# Sheet2.net
KiCad netlist of a schematic drawn in Altium Designer
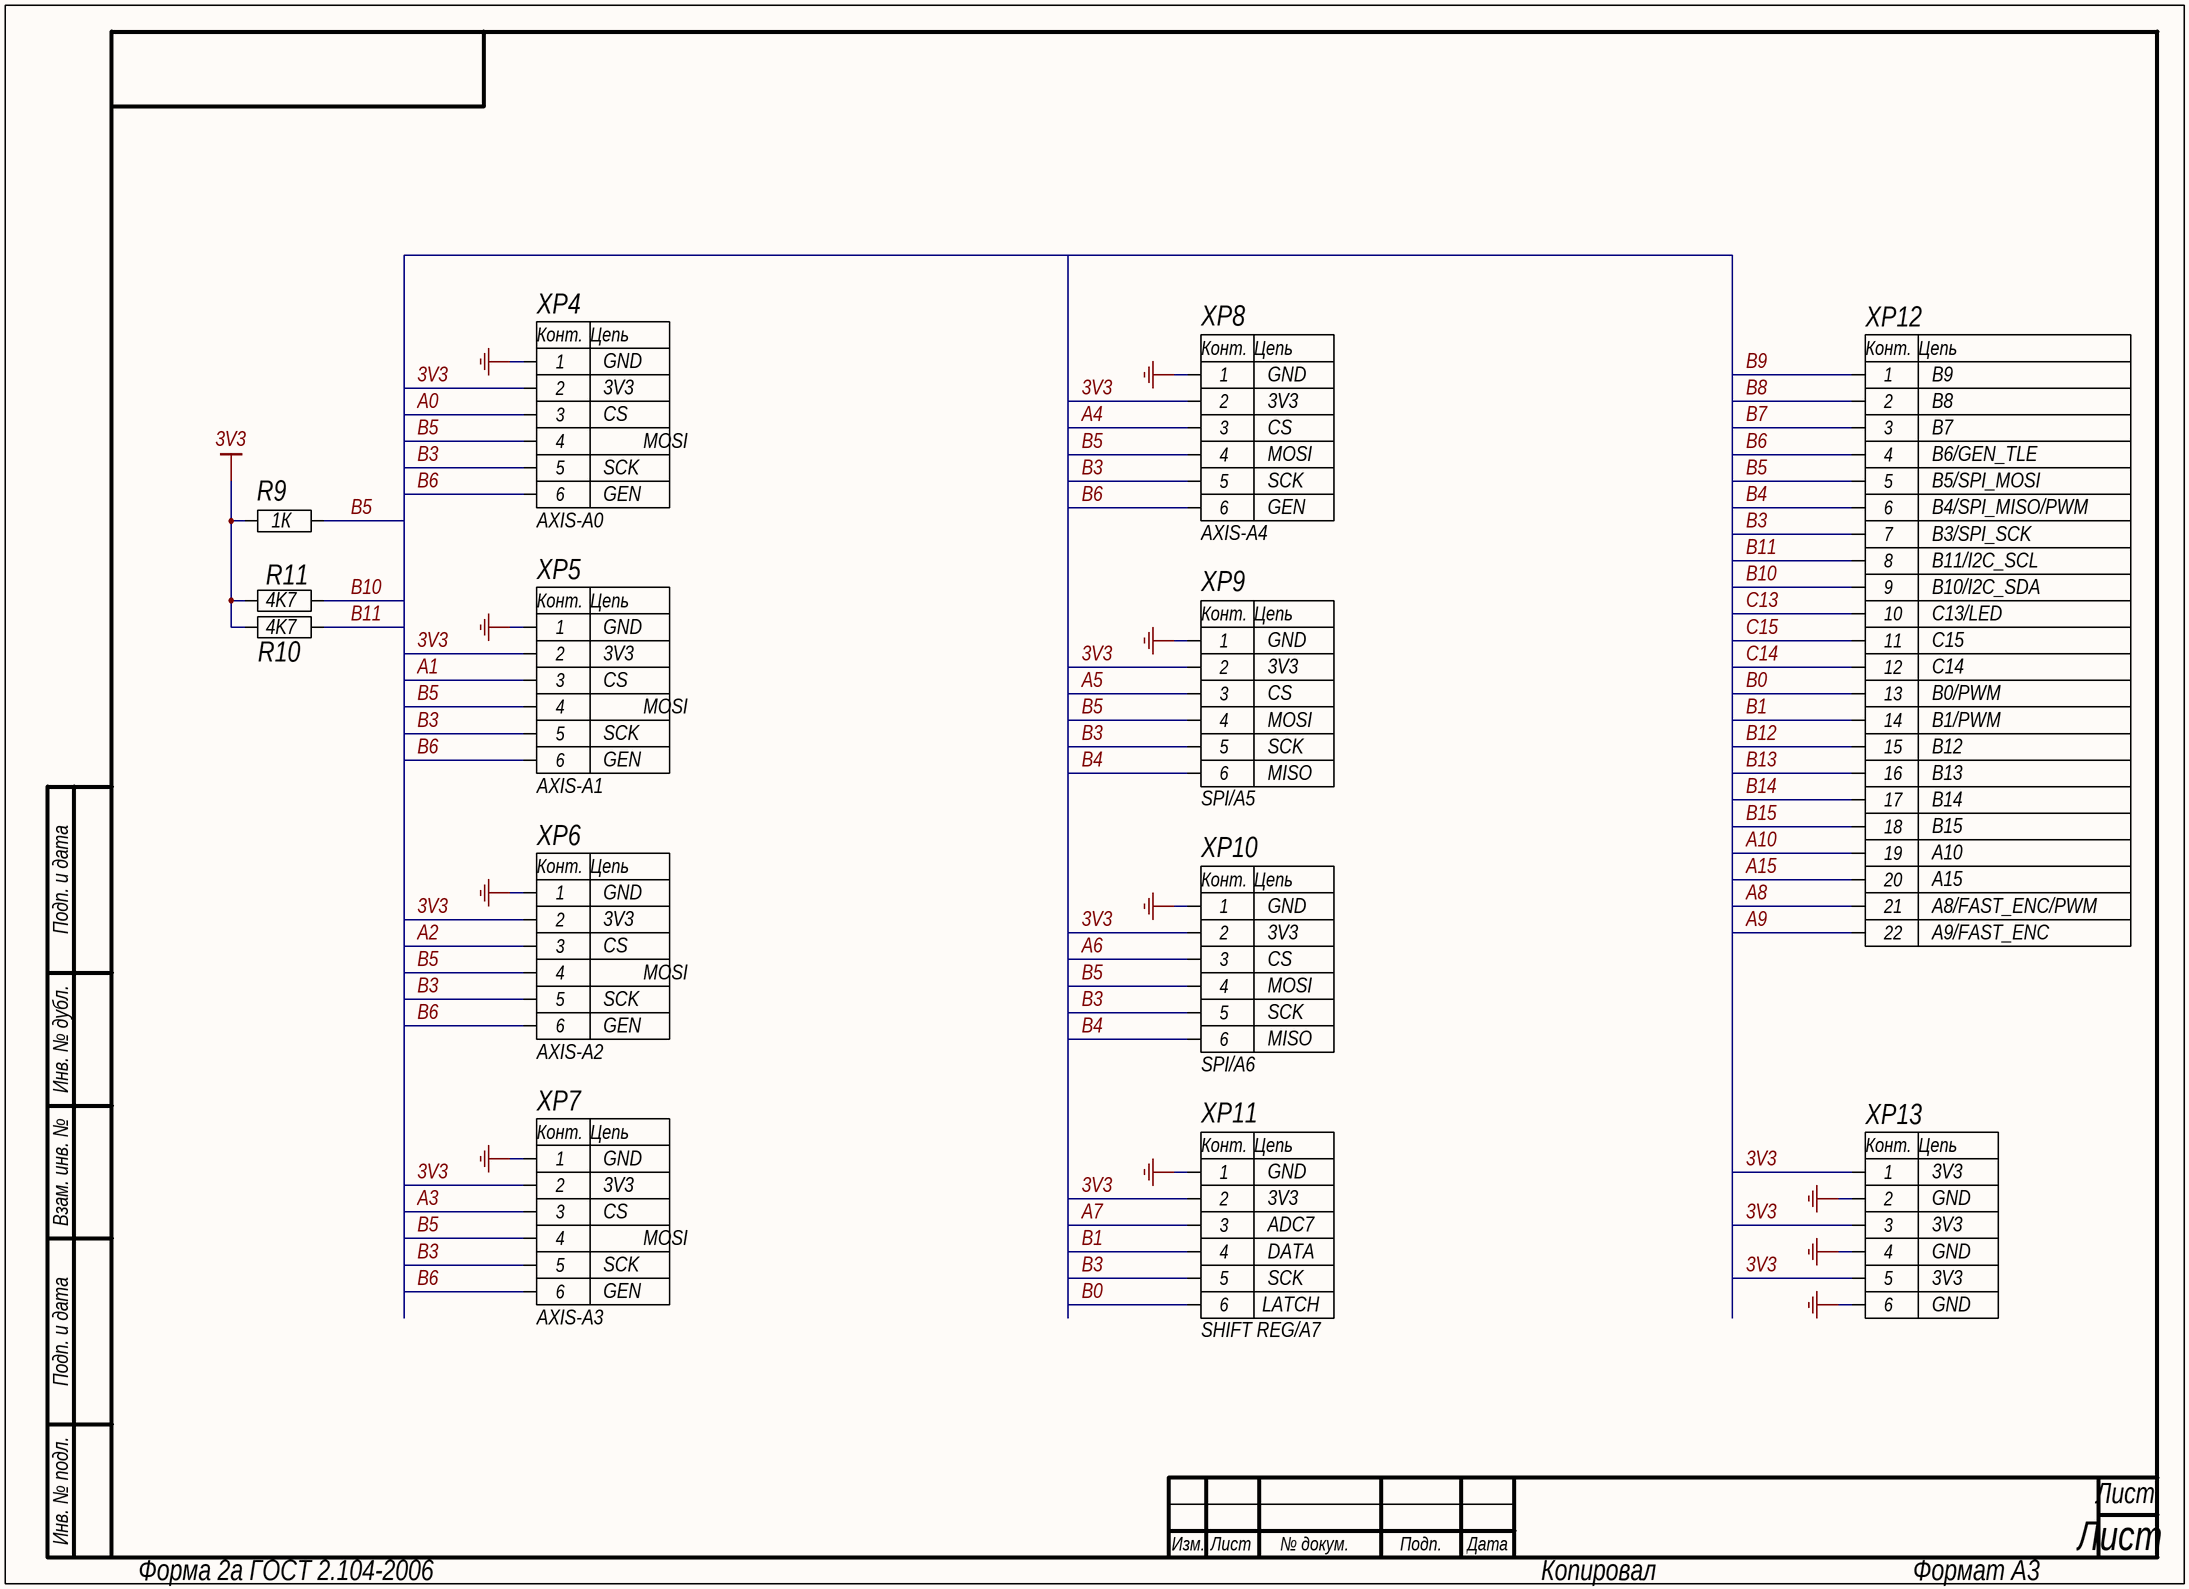
[diagram p0: Sheet2.SchDoc]

(export (version "E")
  (design (tool "Eeschema 10.0.6"))
  (components
    (comp (ref "R9")
      (value "1К")
      (footprint "RC0603_HD")
      (description "1K ± 1%, SMD 0603")
      (libsource (lib "Резисторы") (part "Резистор RC0603FR-071KL"))
    )
    (comp (ref "R10")
      (value "4K7")
      (footprint "RC0603_HD")
      (description "4K7 ± 1%, SMD 0603")
      (libsource (lib "Резисторы") (part "Резистор RC0603FR-074K7L"))
    )
    (comp (ref "R11")
      (value "4K7")
      (footprint "RC0603_HD")
      (description "4K7 ± 1%, SMD 0603")
      (libsource (lib "Резисторы") (part "Резистор RC0603FR-074K7L"))
    )
    (comp (ref "XP4")
      (value "AXIS-A0")
      (footprint "PH2.0-6P")
      (description "PH2.0-6P")
      (libsource (lib "Соединители") (part "Вилка PH2.0-6P"))
    )
    (comp (ref "XP5")
      (value "AXIS-A1")
      (footprint "PH2.0-6P")
      (description "PH2.0-6P")
      (libsource (lib "Соединители") (part "Вилка PH2.0-6P"))
    )
    (comp (ref "XP6")
      (value "AXIS-A2")
      (footprint "PH2.0-6P")
      (description "PH2.0-6P")
      (libsource (lib "Соединители") (part "Вилка PH2.0-6P"))
    )
    (comp (ref "XP7")
      (value "AXIS-A3")
      (footprint "PH2.0-6P")
      (description "PH2.0-6P")
      (libsource (lib "Соединители") (part "Вилка PH2.0-6P"))
    )
    (comp (ref "XP8")
      (value "AXIS-A4")
      (footprint "PH2.0-6P")
      (description "PH2.0-6P")
      (libsource (lib "Соединители") (part "Вилка PH2.0-6P"))
    )
    (comp (ref "XP9")
      (value "SPI/A5")
      (footprint "PH2.0-6P")
      (description "PH2.0-6P")
      (libsource (lib "Соединители") (part "Вилка PH2.0-6P"))
    )
    (comp (ref "XP10")
      (value "SPI/A6")
      (footprint "PH2.0-6P")
      (description "PH2.0-6P")
      (libsource (lib "Соединители") (part "Вилка PH2.0-6P"))
    )
    (comp (ref "XP11")
      (value "SHIFT REG/A7")
      (footprint "PH2.0-6P")
      (description "PH2.0-6P")
      (libsource (lib "Соединители") (part "Вилка PH2.0-6P"))
    )
    (comp (ref "XP12")
      (value "GPIO")
      (footprint "PLD-22")
      (description "PLD-22")
      (libsource (lib "Соединители") (part "Вилка DS1021-2x11"))
    )
    (comp (ref "XP13")
      (value "SUPPLY")
      (footprint "PLD-6")
      (description "PLD-6")
      (libsource (lib "Соединители") (part "Вилка DS1021-2x3"))
    )
  )
  (nets
    (net (code "1") (name "/A0") (class "Default")
      (node (ref "XP4") (pin "3") (pinfunction "3_3") (pintype "passive"))
    )
    (net (code "2") (name "/A1") (class "Default")
      (node (ref "XP5") (pin "3") (pinfunction "3_3") (pintype "passive"))
    )
    (net (code "3") (name "/A2") (class "Default")
      (node (ref "XP6") (pin "3") (pinfunction "3_3") (pintype "passive"))
    )
    (net (code "4") (name "/A3") (class "Default")
      (node (ref "XP7") (pin "3") (pinfunction "3_3") (pintype "passive"))
    )
    (net (code "5") (name "/A4") (class "Default")
      (node (ref "XP8") (pin "3") (pinfunction "3_3") (pintype "passive"))
    )
    (net (code "6") (name "/A5") (class "Default")
      (node (ref "XP9") (pin "3") (pinfunction "3_3") (pintype "passive"))
    )
    (net (code "7") (name "/A6") (class "Default")
      (node (ref "XP10") (pin "3") (pinfunction "3_3") (pintype "passive"))
    )
    (net (code "8") (name "/A7") (class "Default")
      (node (ref "XP11") (pin "3") (pinfunction "3_3") (pintype "passive"))
    )
    (net (code "9") (name "/A8") (class "Default")
      (node (ref "XP12") (pin "21") (pinfunction "21_21") (pintype "passive"))
    )
    (net (code "10") (name "/A9") (class "Default")
      (node (ref "XP12") (pin "22") (pinfunction "22_22") (pintype "passive"))
    )
    (net (code "11") (name "/A10") (class "Default")
      (node (ref "XP12") (pin "19") (pinfunction "19_19") (pintype "passive"))
    )
    (net (code "12") (name "/A15") (class "Default")
      (node (ref "XP12") (pin "20") (pinfunction "20_20") (pintype "passive"))
    )
    (net (code "13") (name "/B0") (class "Default")
      (node (ref "XP11") (pin "6") (pinfunction "6_6") (pintype "passive"))
      (node (ref "XP12") (pin "13") (pinfunction "13_13") (pintype "passive"))
    )
    (net (code "14") (name "/B1") (class "Default")
      (node (ref "XP11") (pin "4") (pinfunction "4_4") (pintype "passive"))
      (node (ref "XP12") (pin "14") (pinfunction "14_14") (pintype "passive"))
    )
    (net (code "15") (name "/B3") (class "Default")
      (node (ref "XP10") (pin "5") (pinfunction "5_5") (pintype "passive"))
      (node (ref "XP11") (pin "5") (pinfunction "5_5") (pintype "passive"))
      (node (ref "XP12") (pin "7") (pinfunction "7_7") (pintype "passive"))
      (node (ref "XP4") (pin "5") (pinfunction "5_5") (pintype "passive"))
      (node (ref "XP5") (pin "5") (pinfunction "5_5") (pintype "passive"))
      (node (ref "XP6") (pin "5") (pinfunction "5_5") (pintype "passive"))
      (node (ref "XP7") (pin "5") (pinfunction "5_5") (pintype "passive"))
      (node (ref "XP8") (pin "5") (pinfunction "5_5") (pintype "passive"))
      (node (ref "XP9") (pin "5") (pinfunction "5_5") (pintype "passive"))
    )
    (net (code "16") (name "/B4") (class "Default")
      (node (ref "XP10") (pin "6") (pinfunction "6_6") (pintype "passive"))
      (node (ref "XP12") (pin "6") (pinfunction "6_6") (pintype "passive"))
      (node (ref "XP9") (pin "6") (pinfunction "6_6") (pintype "passive"))
    )
    (net (code "17") (name "/B5") (class "Default")
      (node (ref "R9") (pin "1") (pinfunction "1_1") (pintype "passive"))
      (node (ref "XP10") (pin "4") (pinfunction "4_4") (pintype "passive"))
      (node (ref "XP12") (pin "5") (pinfunction "5_5") (pintype "passive"))
      (node (ref "XP4") (pin "4") (pinfunction "4_4") (pintype "passive"))
      (node (ref "XP5") (pin "4") (pinfunction "4_4") (pintype "passive"))
      (node (ref "XP6") (pin "4") (pinfunction "4_4") (pintype "passive"))
      (node (ref "XP7") (pin "4") (pinfunction "4_4") (pintype "passive"))
      (node (ref "XP8") (pin "4") (pinfunction "4_4") (pintype "passive"))
      (node (ref "XP9") (pin "4") (pinfunction "4_4") (pintype "passive"))
    )
    (net (code "18") (name "/B6") (class "Default")
      (node (ref "XP12") (pin "4") (pinfunction "4_4") (pintype "passive"))
      (node (ref "XP4") (pin "6") (pinfunction "6_6") (pintype "passive"))
      (node (ref "XP5") (pin "6") (pinfunction "6_6") (pintype "passive"))
      (node (ref "XP6") (pin "6") (pinfunction "6_6") (pintype "passive"))
      (node (ref "XP7") (pin "6") (pinfunction "6_6") (pintype "passive"))
      (node (ref "XP8") (pin "6") (pinfunction "6_6") (pintype "passive"))
    )
    (net (code "19") (name "/B7") (class "Default")
      (node (ref "XP12") (pin "3") (pinfunction "3_3") (pintype "passive"))
    )
    (net (code "20") (name "/B8") (class "Default")
      (node (ref "XP12") (pin "2") (pinfunction "2_2") (pintype "passive"))
    )
    (net (code "21") (name "/B9") (class "Default")
      (node (ref "XP12") (pin "1") (pinfunction "1_1") (pintype "passive"))
    )
    (net (code "22") (name "/B10") (class "Default")
      (node (ref "R11") (pin "2") (pinfunction "2_2") (pintype "passive"))
      (node (ref "XP12") (pin "9") (pinfunction "9_9") (pintype "passive"))
    )
    (net (code "23") (name "/B11") (class "Default")
      (node (ref "R10") (pin "2") (pinfunction "2_2") (pintype "passive"))
      (node (ref "XP12") (pin "8") (pinfunction "8_8") (pintype "passive"))
    )
    (net (code "24") (name "/B12") (class "Default")
      (node (ref "XP12") (pin "15") (pinfunction "15_15") (pintype "passive"))
    )
    (net (code "25") (name "/B13") (class "Default")
      (node (ref "XP12") (pin "16") (pinfunction "16_16") (pintype "passive"))
    )
    (net (code "26") (name "/B14") (class "Default")
      (node (ref "XP12") (pin "17") (pinfunction "17_17") (pintype "passive"))
    )
    (net (code "27") (name "/B15") (class "Default")
      (node (ref "XP12") (pin "18") (pinfunction "18_18") (pintype "passive"))
    )
    (net (code "28") (name "/C13") (class "Default")
      (node (ref "XP12") (pin "10") (pinfunction "10_10") (pintype "passive"))
    )
    (net (code "29") (name "/C14") (class "Default")
      (node (ref "XP12") (pin "12") (pinfunction "12_12") (pintype "passive"))
    )
    (net (code "30") (name "/C15") (class "Default")
      (node (ref "XP12") (pin "11") (pinfunction "11_11") (pintype "passive"))
    )
    (net (code "31") (name "3V3") (class "Default")
      (node (ref "R10") (pin "1") (pinfunction "1_1") (pintype "passive"))
      (node (ref "R11") (pin "1") (pinfunction "1_1") (pintype "passive"))
      (node (ref "R9") (pin "2") (pinfunction "2_2") (pintype "passive"))
      (node (ref "XP10") (pin "2") (pinfunction "2_2") (pintype "passive"))
      (node (ref "XP11") (pin "2") (pinfunction "2_2") (pintype "passive"))
      (node (ref "XP13") (pin "1") (pinfunction "1_1") (pintype "passive"))
      (node (ref "XP13") (pin "3") (pinfunction "3_3") (pintype "passive"))
      (node (ref "XP13") (pin "5") (pinfunction "5_5") (pintype "passive"))
      (node (ref "XP4") (pin "2") (pinfunction "2_2") (pintype "passive"))
      (node (ref "XP5") (pin "2") (pinfunction "2_2") (pintype "passive"))
      (node (ref "XP6") (pin "2") (pinfunction "2_2") (pintype "passive"))
      (node (ref "XP7") (pin "2") (pinfunction "2_2") (pintype "passive"))
      (node (ref "XP8") (pin "2") (pinfunction "2_2") (pintype "passive"))
      (node (ref "XP9") (pin "2") (pinfunction "2_2") (pintype "passive"))
    )
    (net (code "32") (name "GND") (class "Default")
      (node (ref "XP10") (pin "1") (pinfunction "1_1") (pintype "passive"))
      (node (ref "XP11") (pin "1") (pinfunction "1_1") (pintype "passive"))
      (node (ref "XP13") (pin "2") (pinfunction "2_2") (pintype "passive"))
      (node (ref "XP13") (pin "4") (pinfunction "4_4") (pintype "passive"))
      (node (ref "XP13") (pin "6") (pinfunction "6_6") (pintype "passive"))
      (node (ref "XP4") (pin "1") (pinfunction "1_1") (pintype "passive"))
      (node (ref "XP5") (pin "1") (pinfunction "1_1") (pintype "passive"))
      (node (ref "XP6") (pin "1") (pinfunction "1_1") (pintype "passive"))
      (node (ref "XP7") (pin "1") (pinfunction "1_1") (pintype "passive"))
      (node (ref "XP8") (pin "1") (pinfunction "1_1") (pintype "passive"))
      (node (ref "XP9") (pin "1") (pinfunction "1_1") (pintype "passive"))
    )
  )
)
